# AOPIO.net
KiCad netlist of a schematic drawn in Altium Designer
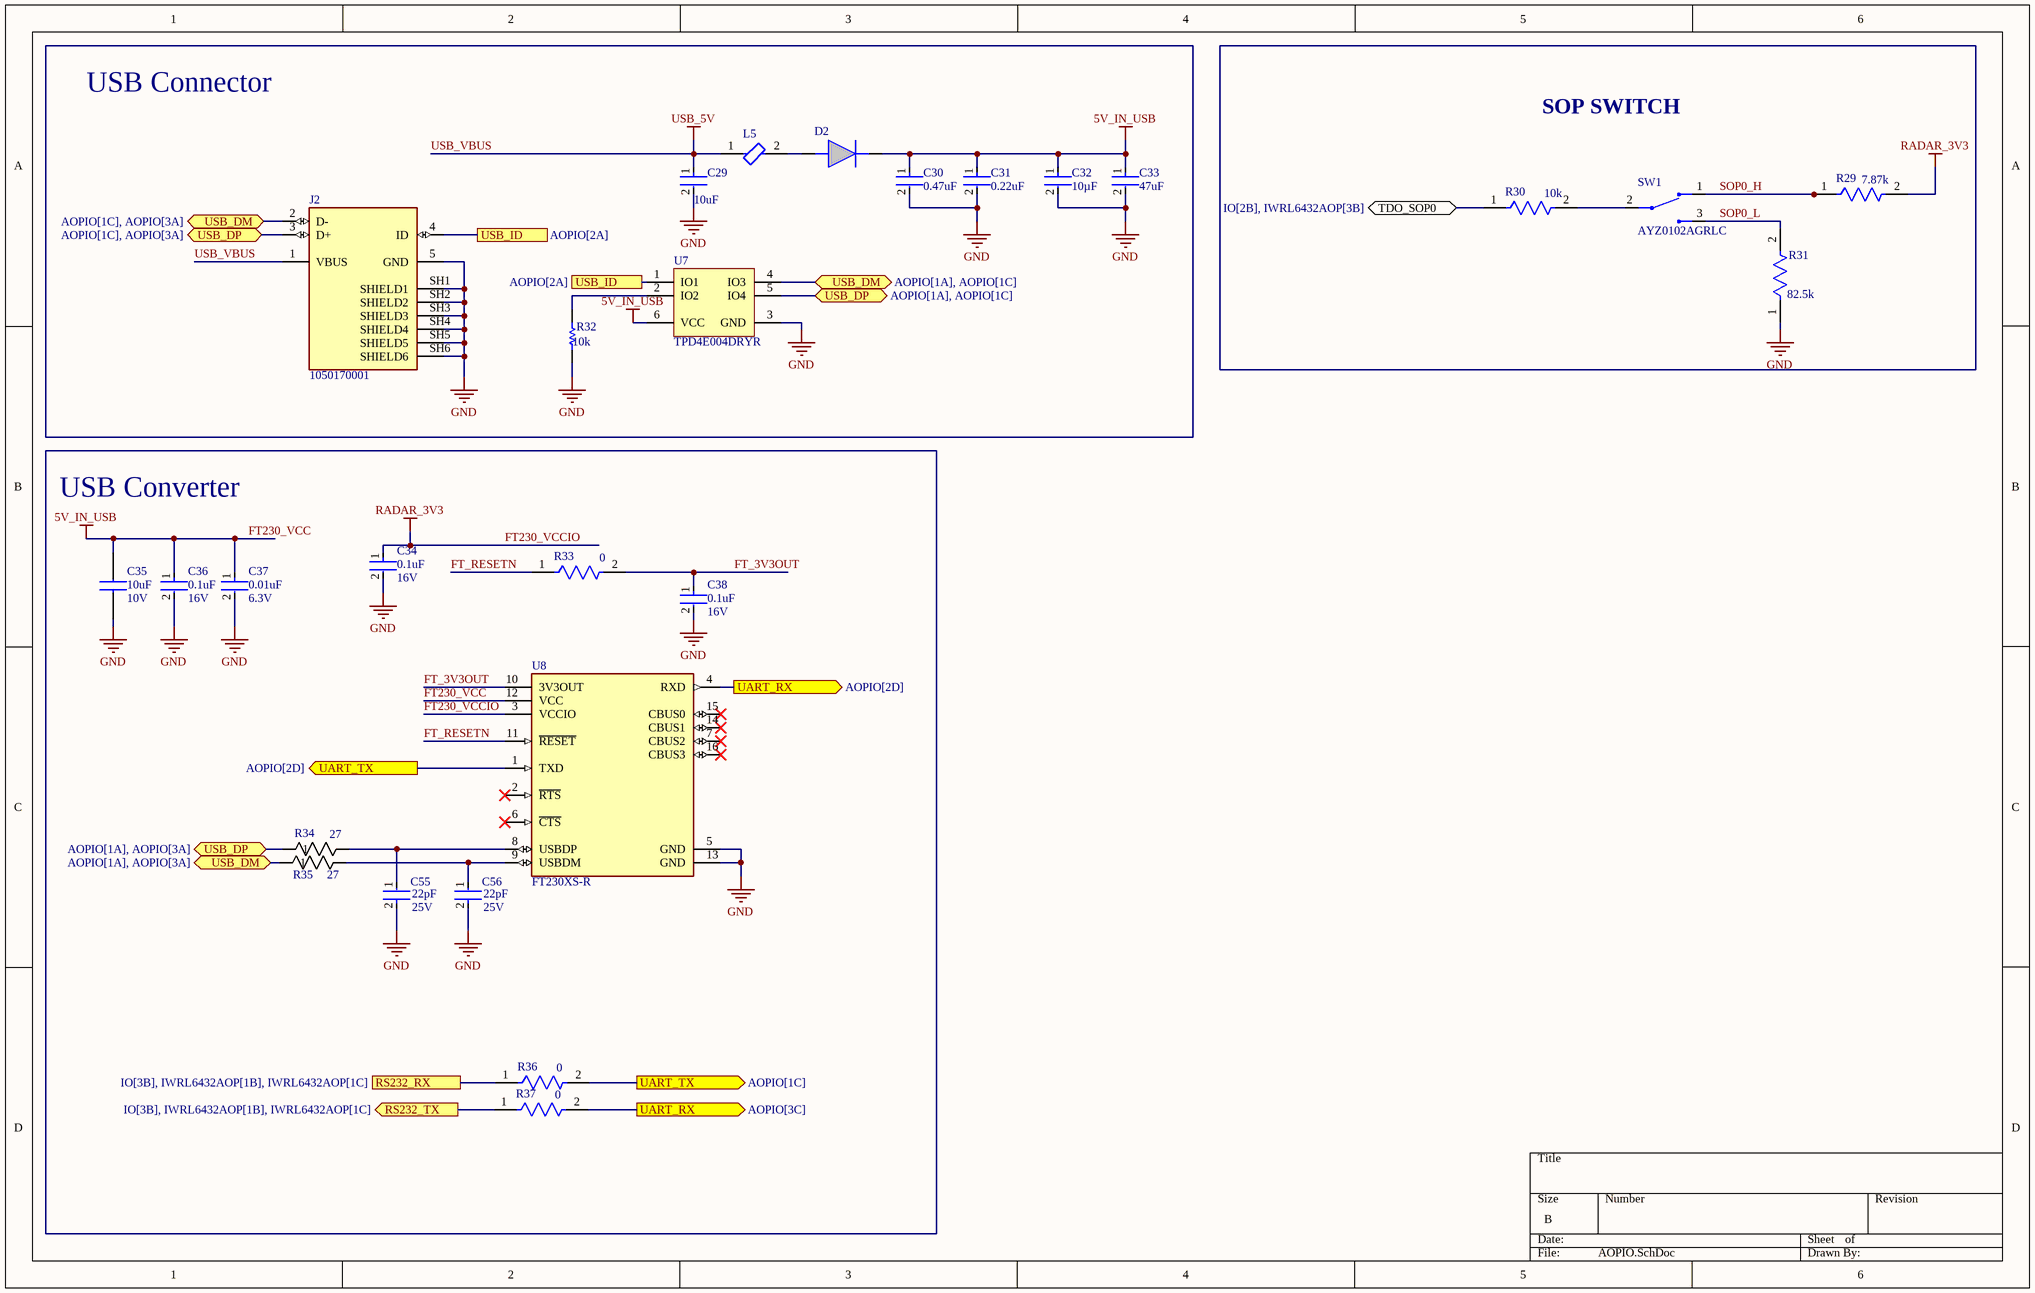
[diagram p0: AOPIO.SchDoc]

(export (version "E")
  (design (tool "Eeschema 10.0.6"))
  (components
    (comp (ref "C29")
      (value "GRT188R61A106KE13D")
      (footprint "FP-GRT188-0_15-IPC_C")
      (description "Multi-Layer Ceramic Capacitor 10uF 10V X5R ±10% 0603 Paper T/R")
      (fields (field (name "CAPACITANCE") "10uF") (field (name "TOLERANCE") "10%"))
      (libsource (lib "Altium Content Vault") (part "02cd4be3c70576c341d710602a673aa"))
    )
    (comp (ref "C30")
      (value "GCM155C71A474ME36J")
      (footprint "FP-GCM155-0_1-IPC_B")
      (description "Ceramic Capacitor for Automotive 470nF ±20% 10VDC X7S 0402 Paper T/R")
      (fields (field (name "CAPACITANCE") "0.47uF"))
      (libsource (lib "Altium Content Vault") (part "11868f565c42a9108669ba33697ecf6"))
    )
    (comp (ref "C31")
      (value "GCM155R71C224KE02D")
      (footprint "FP-GCM155-0_05-MFG")
      (description "Ceramic Capacitor for Automotive 220nF ±10% 16VDC X7R 0402 Paper T/R")
      (fields (field (name "TOLERANCE") "10%") (field (name "CAPACITANCE") "0.22uF"))
      (libsource (lib "Altium Content Vault") (part "02cd4be3c70576c341d710602a673aa"))
    )
    (comp (ref "C32")
      (value "GRM155R61A106ME18D")
      (footprint "FP-GRM155-0_2-MFG")
      (fields (field (name "TOLERANCE") "20%") (field (name "CAPACITANCE") "10µF"))
      (libsource (lib "Altium Content Vault") (part "b4654b650e69147ec39a6b967a45e02"))
    )
    (comp (ref "C33")
      (value "GRM31CR61A476ME15L")
      (footprint "FP-GRM31C-0_2-e0_3_0_8-IPC_C")
      (description "Chip Multilayer Ceramic Capacitors for General Purpose, 1206, 47uF, X5R, 15%, 20%, 10V")
      (fields
        (field (name "CAPACITANCE") "47uF")
        (field (name "TOLERANCE") "20%")
        (field (name "VOLTAGE") "10V")
      )
      (libsource (lib "Altium Content Vault") (part "02cd4be3c70576c341d710602a673aa"))
    )
    (comp (ref "C34")
      (value "GRM033R61C104ME14D")
      (footprint "FP-GRM033-0_03-IPC_C")
      (description "Chip Multilayer Ceramic Capacitors for General Purpose, 0201, 0.10uF, X5R, 15%, 20%, 16V")
      (fields
        (field (name "CAPACITANCE") "0.1uF")
        (field (name "TOLERANCE") "20%")
        (field (name "VOLTAGE RATING (DC)") "16V")
      )
      (libsource (lib "Altium Content Vault") (part "b4654b650e69147ec39a6b967a45e02"))
    )
    (comp (ref "C35")
      (value "0402ZD106MAT2A")
      (footprint "CAPC1005X56N")
      (description "Multilayer Ceramic Capacitors MLCC - SMD/SMT 10V 10uF X5R 0402 20% Tol")
      (fields
        (field (name "MOUSER PART NUMBER") "581-0402ZD106MAT2A")
        (field (name "CAPACITANCE") "10uF")
        (field (name "VOLTAGE") "10V")
      )
      (libsource (lib "0402ZD106MAT2A") (part "0402ZD106MAT2A"))
    )
    (comp (ref "C36")
      (value "GRM033R61C104ME14D")
      (footprint "FP-GRM033-0_03-IPC_C")
      (description "Chip Multilayer Ceramic Capacitors for General Purpose, 0201, 0.10uF, X5R, 15%, 20%, 16V")
      (fields
        (field (name "CAPACITANCE") "0.1uF")
        (field (name "TOLERANCE") "20%")
        (field (name "VOLTAGE RATING (DC)") "16V")
      )
      (libsource (lib "Altium Content Vault") (part "b4654b650e69147ec39a6b967a45e02"))
    )
    (comp (ref "C37")
      (value "GRM033R70J103KA01D")
      (footprint "FP-GRM033-0_03-IPC_A")
      (description "Chip Multilayer Ceramic Capacitors for General Purpose, 0201, 10000pF, X7R, 15%, 10%, 6.3V")
      (fields
        (field (name "TOLERANCE") "10%")
        (field (name "VOLTAGE RATING (DC)") "6.3V")
        (field (name "VOLTAGE") "6.3V")
        (field (name "CAPACITANCE") "0.01uF")
      )
      (libsource (lib "Altium Content Vault") (part "b4654b650e69147ec39a6b967a45e02"))
    )
    (comp (ref "C38")
      (value "GRM033R61C104ME14D")
      (footprint "FP-GRM033-0_03-IPC_C")
      (description "Chip Multilayer Ceramic Capacitors for General Purpose, 0201, 0.10uF, X5R, 15%, 20%, 16V")
      (fields
        (field (name "CAPACITANCE") "0.1uF")
        (field (name "TOLERANCE") "20%")
        (field (name "VOLTAGE RATING (DC)") "16V")
      )
      (libsource (lib "Altium Content Vault") (part "b4654b650e69147ec39a6b967a45e02"))
    )
    (comp (ref "C55")
      (value "GCM0335C1E220JA16D")
      (footprint "FP-GCM033-0_03-IPC_B")
      (description "Ceramic Capacitor for Automotive 22pF  ±5% 25VDC C0G 0201 Paper T/R")
      (fields (field (name "VOLTAGE") "25V") (field (name "CAPACITANCE") "22pF"))
      (libsource (lib "Altium Content Vault") (part "f23184f103b6ebe33a8c269c53dcba6"))
    )
    (comp (ref "C56")
      (value "GCM0335C1E220JA16D")
      (footprint "FP-GCM033-0_03-IPC_B")
      (description "Ceramic Capacitor for Automotive 22pF  ±5% 25VDC C0G 0201 Paper T/R")
      (fields (field (name "VOLTAGE") "25V") (field (name "CAPACITANCE") "22pF"))
      (libsource (lib "Altium Content Vault") (part "f23184f103b6ebe33a8c269c53dcba6"))
    )
    (comp (ref "D2")
      (value "PMEG3020EP_115")
      (footprint "SODFL4725X110N")
      (description "Schottky Diodes & Rectifiers SCHOTTKY RECT 30V 2A")
      (fields
        (field (name "MANUFACTURER_PART_NUMBER") "PMEG3020EP,115")
        (field (name "MOUSER PART NUMBER") "771-PMEG3020EP115")
      )
      (libsource (lib "PMEG3020EP_115") (part "PMEG3020EP_115"))
    )
    (comp (ref "J2")
      (value "1050170001")
      (footprint "MOLEX_1050170001")
      (description "USB - micro B USB 2.0 Receptacle Connector 5 Position Surface Mount, Right Angle; Through Hole")
      (fields (field (name "MF") "Molex"))
      (libsource (lib "1050170001") (part "1050170001"))
    )
    (comp (ref "L5")
      (value "BLM15PD300SZ1D")
      (footprint "FP-BLM15-0_05-d0_7-IPC_A")
      (description "Chip Ferrite Bead, 0402, 30Ω @ 100MHz, 0.035Ω, 25%, 2.2A")
      (libsource (lib "Altium Content Vault") (part "5f30dd21d616792df468990f7003faa"))
    )
    (comp (ref "R29")
      (value "CRCW04027K87FKED")
      (footprint "FP-CRCW0402-e3-MFG")
      (description "RES Thick Film, 7.87kΩ, 1%, 0.063W, 100ppm/°C, 0402")
      (fields (field (name "TOLERANCE") "1%") (field (name "RESISTANCE") "7.87k"))
      (libsource (lib "Altium Content Vault") (part "1029c3af85768c4190bb7ad29bc67b5"))
    )
    (comp (ref "R30")
      (value "CRCW040210K0FKEDC")
      (footprint "FP-CRCW0402-C-e3-IPC_C")
      (description "RES 10K OHM 1% 1/16W 0402")
      (fields (field (name "TOLERANCE") "1%") (field (name "RESISTANCE") "10k"))
      (libsource (lib "Altium Content Vault") (part "1029c3af85768c4190bb7ad29bc67b5"))
    )
    (comp (ref "R31")
      (value "CRCW040282K5FKED")
      (footprint "FP-CRCW0402-e3-MFG")
      (description "RES Thick Film, 82.5kΩ, 1%, 0.063W, 100ppm/°C, 0402")
      (fields (field (name "RESISTANCE") "82.5k") (field (name "TOLERANCE") "1%"))
      (libsource (lib "Altium Content Vault") (part "1029c3af85768c4190bb7ad29bc67b5"))
    )
    (comp (ref "R32")
      (value "CRCW040210K0FKEDHP")
      (footprint "RESC1005X40X25ML05T10")
      (fields (field (name "MANUFACTURER") "Vishay Dale") (field (name "RESISTANCE") "10k"))
      (libsource (lib "Altium Content Vault") (part "RES"))
    )
    (comp (ref "R33")
      (value "RC0402JR-070RP")
      (footprint "FP-RC0402-0_4-MFG")
      (description "RES SMD 0 OHM JUMPER 1/16W 0402")
      (fields (field (name "RESISTANCE") "0"))
      (libsource (lib "Altium Content Vault") (part "1029c3af85768c4190bb7ad29bc67b5"))
    )
    (comp (ref "R34")
      (value "RC0201JR-0727RL")
      (footprint "RES_RC0201_P6XP3_YAG")
      (description "No Description Available")
      (fields
        (field (name "RESISTANCE") "27")
        (field (name "COPYRIGHT") "Copyright (C) 2026 Ultra Librarian. All rights reserved.")
      )
      (libsource (lib "RC0201JR-0727RL") (part "RC0201JR-0727RL"))
    )
    (comp (ref "R35")
      (value "RC0201JR-0727RL")
      (footprint "RES_RC0201_P6XP3_YAG")
      (description "No Description Available")
      (fields
        (field (name "RESISTANCE") "27")
        (field (name "COPYRIGHT") "Copyright (C) 2026 Ultra Librarian. All rights reserved.")
      )
      (libsource (lib "RC0201JR-0727RL") (part "RC0201JR-0727RL"))
    )
    (comp (ref "R36")
      (value "RC0402JR-070RP")
      (footprint "FP-RC0402-0_4-MFG")
      (description "RES SMD 0 OHM JUMPER 1/16W 0402")
      (fields (field (name "RESISTANCE") "0"))
      (libsource (lib "Altium Content Vault") (part "1029c3af85768c4190bb7ad29bc67b5"))
    )
    (comp (ref "R37")
      (value "RC0402JR-070RP")
      (footprint "FP-RC0402-0_4-MFG")
      (description "RES SMD 0 OHM JUMPER 1/16W 0402")
      (fields (field (name "RESISTANCE") "0"))
      (libsource (lib "Altium Content Vault") (part "1029c3af85768c4190bb7ad29bc67b5"))
    )
    (comp (ref "SW1")
      (value "AYZ0102AGRLC")
      (footprint "SW_AYZ0102AGRLC")
      (description "Slide Switch SPDT Surface Mount, Right Angle")
      (fields (field (name "DIGI-KEY_PART_NUMBER") "401-2012-1-ND") (field (name "MF") "C&K"))
      (libsource (lib "AYZ0102AGRLC") (part "AYZ0102AGRLC"))
    )
    (comp (ref "U7")
      (value "TPD4E004DRYR")
      (footprint "DRY0006A")
      (fields (field (name "MANUFACTURER") "Texas Instruments"))
      (libsource (lib "Altium Content Vault") (part "TI-TPD4E004-SON_DRY-6"))
    )
    (comp (ref "U8")
      (value "FT230XS-R")
      (footprint "FP-SSOP-16-MFG")
      (description "IC USB SERIAL BASIC UART 16SSOP")
      (libsource (lib "Altium Content Vault") (part "33f179d67b5e33a3acba2e4c59411a5"))
    )
  )
  (nets
    (net (code "1") (name "/FT_3V3OUT") (class "Default")
      (node (ref "C38") (pin "1") (pinfunction "1_1") (pintype "passive"))
      (node (ref "R33") (pin "2") (pinfunction "2_2") (pintype "passive"))
      (node (ref "U8") (pin "10") (pinfunction "3V3OUT_10") (pintype "power_in"))
    )
    (net (code "2") (name "/FT_RESETN") (class "Default")
      (node (ref "R33") (pin "1") (pinfunction "1_1") (pintype "passive"))
      (node (ref "U8") (pin "11") (pinfunction "~{RESET}_11") (pintype "input"))
    )
    (net (code "3") (name "/RS232_RX") (class "Default")
      (node (ref "R36") (pin "1") (pinfunction "1_1") (pintype "passive"))
    )
    (net (code "4") (name "/RS232_TX") (class "Default")
      (node (ref "R37") (pin "1") (pinfunction "1_1") (pintype "passive"))
    )
    (net (code "5") (name "/SOP0_H") (class "Default")
      (node (ref "R29") (pin "1") (pinfunction "1_1") (pintype "passive"))
      (node (ref "SW1") (pin "1") (pinfunction "1_1") (pintype "passive"))
    )
    (net (code "6") (name "/SOP0_L") (class "Default")
      (node (ref "R31") (pin "2") (pinfunction "2_2") (pintype "passive"))
      (node (ref "SW1") (pin "3") (pinfunction "3_3") (pintype "passive"))
    )
    (net (code "7") (name "/TDO_SOP0") (class "Default")
      (node (ref "R30") (pin "1") (pinfunction "1_1") (pintype "passive"))
    )
    (net (code "8") (name "/UART_RX") (class "Default")
      (node (ref "R37") (pin "2") (pinfunction "2_2") (pintype "passive"))
      (node (ref "U8") (pin "4") (pinfunction "RXD_4") (pintype "output"))
    )
    (net (code "9") (name "/UART_TX") (class "Default")
      (node (ref "R36") (pin "2") (pinfunction "2_2") (pintype "passive"))
      (node (ref "U8") (pin "1") (pinfunction "TXD_1") (pintype "input"))
    )
    (net (code "10") (name "/USB_DM") (class "Default")
      (node (ref "J2") (pin "2") (pinfunction "D-_2") (pintype "bidirectional"))
      (node (ref "R35") (pin "1") (pinfunction "1_1") (pintype "passive"))
      (node (ref "U7") (pin "4") (pinfunction "IO3_4") (pintype "passive"))
    )
    (net (code "11") (name "/USB_DP") (class "Default")
      (node (ref "J2") (pin "3") (pinfunction "D+_3") (pintype "bidirectional"))
      (node (ref "R34") (pin "1") (pinfunction "1_1") (pintype "passive"))
      (node (ref "U7") (pin "5") (pinfunction "IO4_5") (pintype "passive"))
    )
    (net (code "12") (name "/USB_ID") (class "Default")
      (node (ref "J2") (pin "4") (pinfunction "ID_4") (pintype "bidirectional"))
      (node (ref "U7") (pin "1") (pinfunction "IO1_1") (pintype "passive"))
    )
    (net (code "13") (name "5V_IN_USB") (class "Default")
      (node (ref "C30") (pin "1") (pinfunction "1_1") (pintype "passive"))
      (node (ref "C31") (pin "1") (pinfunction "1_1") (pintype "passive"))
      (node (ref "C32") (pin "1") (pinfunction "1_1") (pintype "passive"))
      (node (ref "C33") (pin "1") (pinfunction "1_1") (pintype "passive"))
      (node (ref "C35") (pin "2") (pinfunction "2_2") (pintype "passive"))
      (node (ref "C36") (pin "1") (pinfunction "1_1") (pintype "passive"))
      (node (ref "C37") (pin "1") (pinfunction "1_1") (pintype "passive"))
      (node (ref "D2") (pin "1") (pinfunction "K_1") (pintype "passive"))
      (node (ref "U7") (pin "6") (pinfunction "VCC_6") (pintype "power_in"))
      (node (ref "U8") (pin "12") (pinfunction "VCC_12") (pintype "power_in"))
    )
    (net (code "14") (name "GND") (class "Default")
      (node (ref "C29") (pin "2") (pinfunction "2_2") (pintype "passive"))
      (node (ref "C30") (pin "2") (pinfunction "2_2") (pintype "passive"))
      (node (ref "C31") (pin "2") (pinfunction "2_2") (pintype "passive"))
      (node (ref "C32") (pin "2") (pinfunction "2_2") (pintype "passive"))
      (node (ref "C33") (pin "2") (pinfunction "2_2") (pintype "passive"))
      (node (ref "C34") (pin "2") (pinfunction "2_2") (pintype "passive"))
      (node (ref "C35") (pin "1") (pinfunction "1_1") (pintype "passive"))
      (node (ref "C36") (pin "2") (pinfunction "2_2") (pintype "passive"))
      (node (ref "C37") (pin "2") (pinfunction "2_2") (pintype "passive"))
      (node (ref "C38") (pin "2") (pinfunction "2_2") (pintype "passive"))
      (node (ref "C55") (pin "2") (pinfunction "2_2") (pintype "passive"))
      (node (ref "C56") (pin "2") (pinfunction "2_2") (pintype "passive"))
      (node (ref "J2") (pin "5") (pinfunction "GND_5") (pintype "power_in"))
      (node (ref "J2") (pin "SH1") (pinfunction "SHIELD1_SH1") (pintype "passive"))
      (node (ref "J2") (pin "SH2") (pinfunction "SHIELD2_SH2") (pintype "passive"))
      (node (ref "J2") (pin "SH3") (pinfunction "SHIELD3_SH3") (pintype "passive"))
      (node (ref "J2") (pin "SH4") (pinfunction "SHIELD4_SH4") (pintype "passive"))
      (node (ref "J2") (pin "SH5") (pinfunction "SHIELD5_SH5") (pintype "passive"))
      (node (ref "J2") (pin "SH6") (pinfunction "SHIELD6_SH6") (pintype "passive"))
      (node (ref "R31") (pin "1") (pinfunction "1_1") (pintype "passive"))
      (node (ref "R32") (pin "1") (pinfunction "1_1") (pintype "passive"))
      (node (ref "U7") (pin "3") (pinfunction "GND_3") (pintype "power_in"))
      (node (ref "U8") (pin "13") (pinfunction "GND_13") (pintype "power_in"))
      (node (ref "U8") (pin "5") (pinfunction "GND_5") (pintype "power_in"))
    )
    (net (code "15") (name "Net-(D2-A)") (class "Default")
      (node (ref "D2") (pin "2") (pinfunction "A_2") (pintype "passive"))
      (node (ref "L5") (pin "2") (pinfunction "2_2") (pintype "passive"))
    )
    (net (code "16") (name "Net-(R30-Pad2)") (class "Default")
      (node (ref "R30") (pin "2") (pinfunction "2_2") (pintype "passive"))
      (node (ref "SW1") (pin "2") (pinfunction "2_2") (pintype "passive"))
    )
    (net (code "17") (name "Net-(U7-IO2)") (class "Default")
      (node (ref "R32") (pin "2") (pinfunction "2_2") (pintype "passive"))
      (node (ref "U7") (pin "2") (pinfunction "IO2_2") (pintype "passive"))
    )
    (net (code "18") (name "Net-(U8-USBDM)") (class "Default")
      (node (ref "C56") (pin "1") (pinfunction "1_1") (pintype "passive"))
      (node (ref "R35") (pin "2") (pinfunction "2_2") (pintype "passive"))
      (node (ref "U8") (pin "9") (pinfunction "USBDM_9") (pintype "bidirectional"))
    )
    (net (code "19") (name "Net-(U8-USBDP)") (class "Default")
      (node (ref "C55") (pin "1") (pinfunction "1_1") (pintype "passive"))
      (node (ref "R34") (pin "2") (pinfunction "2_2") (pintype "passive"))
      (node (ref "U8") (pin "8") (pinfunction "USBDP_8") (pintype "bidirectional"))
    )
    (net (code "20") (name "RADAR_3V3") (class "Default")
      (node (ref "C34") (pin "1") (pinfunction "1_1") (pintype "passive"))
      (node (ref "R29") (pin "2") (pinfunction "2_2") (pintype "passive"))
      (node (ref "U8") (pin "3") (pinfunction "VCCIO_3") (pintype "power_in"))
    )
    (net (code "21") (name "USB_5V") (class "Default")
      (node (ref "C29") (pin "1") (pinfunction "1_1") (pintype "passive"))
      (node (ref "J2") (pin "1") (pinfunction "VBUS_1") (pintype "power_in"))
      (node (ref "L5") (pin "1") (pinfunction "1_1") (pintype "passive"))
    )
    (net (code "22") (name "unconnected-(U8-CBUS0-Pad15)") (class "Default")
      (node (ref "U8") (pin "15") (pinfunction "CBUS0_15") (pintype "bidirectional+no_connect"))
    )
    (net (code "23") (name "unconnected-(U8-CBUS1-Pad14)") (class "Default")
      (node (ref "U8") (pin "14") (pinfunction "CBUS1_14") (pintype "bidirectional+no_connect"))
    )
    (net (code "24") (name "unconnected-(U8-CBUS2-Pad7)") (class "Default")
      (node (ref "U8") (pin "7") (pinfunction "CBUS2_7") (pintype "bidirectional+no_connect"))
    )
    (net (code "25") (name "unconnected-(U8-CBUS3-Pad16)") (class "Default")
      (node (ref "U8") (pin "16") (pinfunction "CBUS3_16") (pintype "bidirectional+no_connect"))
    )
    (net (code "26") (name "unconnected-(U8-~{CTS}-Pad6)") (class "Default")
      (node (ref "U8") (pin "6") (pinfunction "~{CTS}_6") (pintype "input+no_connect"))
    )
    (net (code "27") (name "unconnected-(U8-~{RTS}-Pad2)") (class "Default")
      (node (ref "U8") (pin "2") (pinfunction "~{RTS}_2") (pintype "input+no_connect"))
    )
  )
)
